# Part1_4.net
KiCad netlist of a schematic drawn in Altium Designer
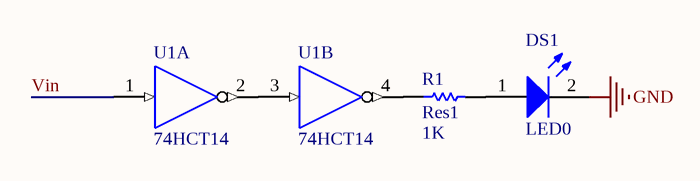
[diagram p0: Part1.4.SchDoc]

(export (version "E")
  (design (tool "Eeschema 10.0.6"))
  (components
    (comp (ref "DS1")
      (value "LED0")
      (footprint "LED-0")
      (description "Typical INFRARED GaAs LED")
      (fields
        (field (name "MANUFACTURER") "Generic Components")
        (field (name "PUBLISHER") "Altium Hobart Technology Centre")
      )
      (libsource (lib "ME218_BaseLib") (part "LED0"))
    )
    (comp (ref "R1")
      (value "Res1")
      (footprint "AXIAL-0.3")
      (description "Resistor")
      (fields
        (field (name "MANUFACTURER") "Generic Components")
        (field (name "ALTIUM_VALUE") "1K")
        (field (name "PUBLISHER") "Altium Hobart Technology Centre")
      )
      (libsource (lib "ME218_BaseLib") (part "Res1"))
    )
    (comp (ref "U1")
      (value "74HCT14")
      (footprint "DIP-14/D19.7")
      (description "Hex Inverter with Schmitt Trigger Input")
      (fields
        (field (name "MANUFACTURER") "Fairchild Semiconductor")
        (field (name "PUBLISHER") "Altium Hobart Technology Centre")
      )
      (libsource (lib "ME218_BaseLib") (part "74xxx14"))
    )
  )
  (nets
    (net (code "1") (name "/Vin") (class "Default")
      (node (ref "U1") (pin "1") (pinfunction "I_1") (pintype "input"))
    )
    (net (code "2") (name "GND") (class "Default")
      (node (ref "DS1") (pin "2") (pinfunction "K_2") (pintype "passive"))
      (node (ref "U1") (pin "7") (pinfunction "GND_7") (pintype "power_in"))
    )
    (net (code "3") (name "Net-(DS1-A)") (class "Default")
      (node (ref "DS1") (pin "1") (pinfunction "A_1") (pintype "passive"))
      (node (ref "R1") (pin "2") (pinfunction "2_2") (pintype "passive"))
    )
    (net (code "4") (name "Net-(U1A-~{O})") (class "Default")
      (node (ref "U1") (pin "2") (pinfunction "~{O}_2") (pintype "output"))
      (node (ref "U1") (pin "3") (pinfunction "I_3") (pintype "input"))
    )
    (net (code "5") (name "Net-(U1B-~{O})") (class "Default")
      (node (ref "R1") (pin "1") (pinfunction "1_1") (pintype "passive"))
      (node (ref "U1") (pin "4") (pinfunction "~{O}_4") (pintype "output"))
    )
    (net (code "6") (name "VCC") (class "Default")
      (node (ref "U1") (pin "14") (pinfunction "VCC_14") (pintype "power_in"))
    )
  )
)
